# PWR_PROT.net
KiCad netlist of a schematic drawn in Altium Designer
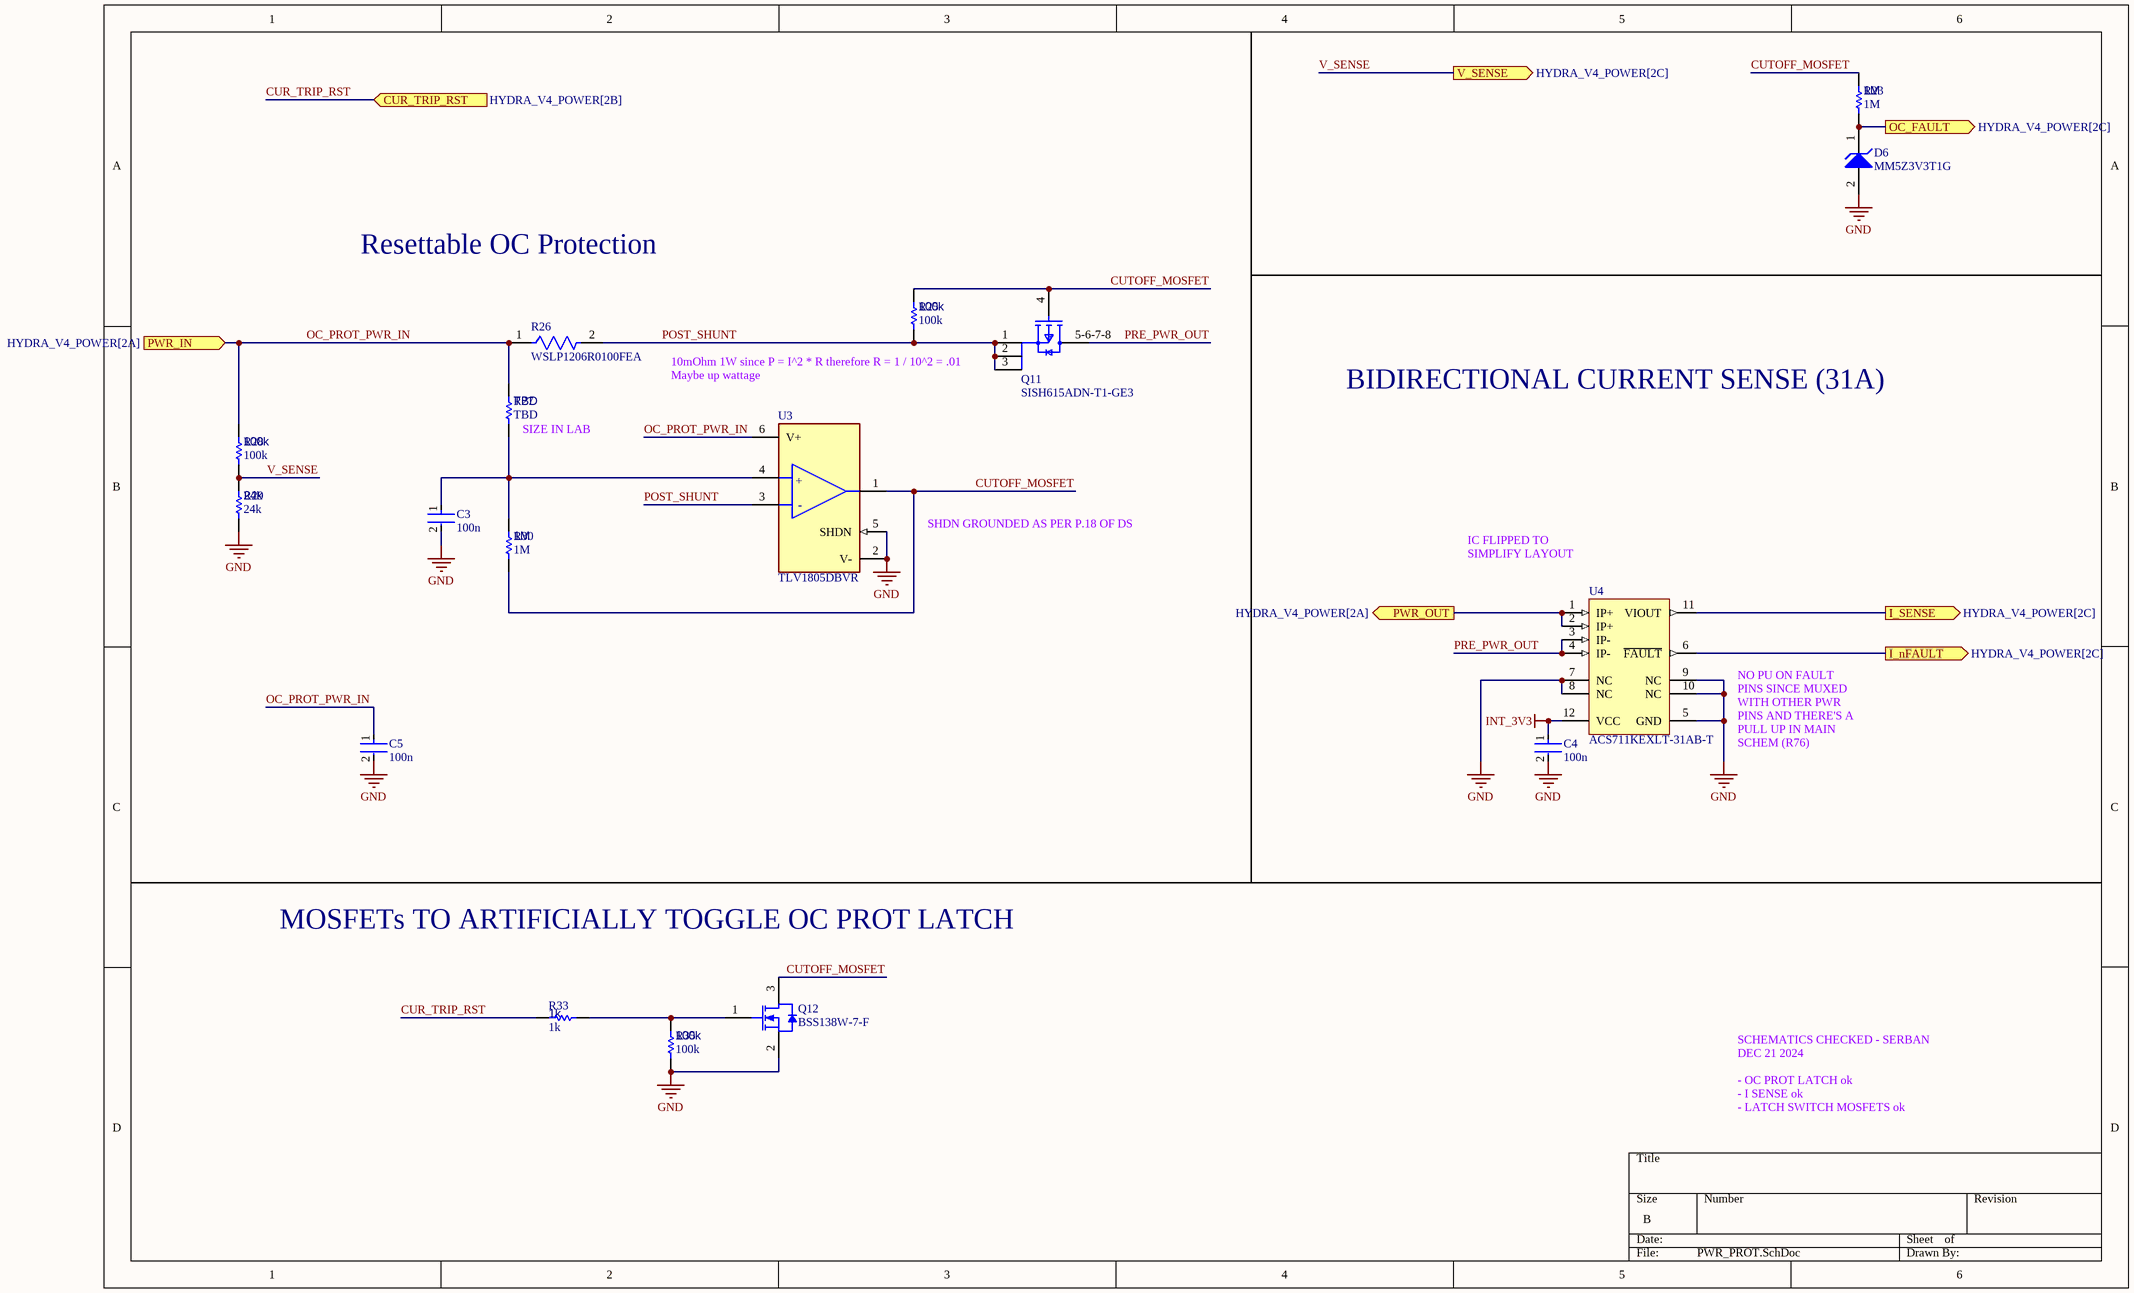
[diagram p0: PWR_PROT.SchDoc]

(export (version "E")
  (design (tool "Eeschema 10.0.6"))
  (components
    (comp (ref "C3")
      (value "100n")
      (footprint "FP-0402-L_1_0_0_05-W_0_5-IPC_A")
      (description "LARGE PADS, 0402 CAP, CHANGE COMMENT TO MATCH REAL P/N")
      (libsource (lib "Space Concordia") (part "b4654b650e69147ec39a6b967a45e02"))
    )
    (comp (ref "C4")
      (value "100n")
      (footprint "FP-0402-L_1_0_0_05-W_0_5-IPC_A")
      (description "LARGE PADS, 0402 CAP, CHANGE COMMENT TO MATCH REAL P/N")
      (libsource (lib "Space Concordia") (part "b4654b650e69147ec39a6b967a45e02"))
    )
    (comp (ref "C5")
      (value "100n")
      (footprint "FP-0402-L_1_0_0_05-W_0_5-IPC_A")
      (description "LARGE PADS, 0402 CAP, CHANGE COMMENT TO MATCH REAL P/N")
      (libsource (lib "Space Concordia") (part "b4654b650e69147ec39a6b967a45e02"))
    )
    (comp (ref "D6")
      (value "MM5Z3V3T1G")
      (footprint "ONSC-SOD-523-2-502-01_V")
      (description "Zener Voltage Regulator, 500 mW, 2-Pin SOD-523, Pb-Free, Tape and Reel")
      (fields (field (name "MANUFACTURER") "On Semiconductor"))
      (libsource (lib "Altium Content Vault") (part "ONSC-K1A2-2"))
    )
    (comp (ref "Q11")
      (value "SISH615ADN-T1-GE3")
      (footprint "SISH615ADN-T1-GE3-Footprint-1")
      (description "Trans MOSFET P-CH 20V 22.1A 8-Pin PowerPAK 1212 EP T/R")
      (libsource (lib "Space Concordia") (part "CMP-013-00036-4"))
    )
    (comp (ref "Q12")
      (value "BSS138W-7-F")
      (footprint "DIOD-SOT323-3_V")
      (fields (field (name "MANUFACTURER") "DiodesIncorporated"))
      (libsource (lib "Altium Content Vault") (part "NEMOS-GSD-3"))
    )
    (comp (ref "R23")
      (value "1M")
      (footprint "R0603B")
      (description "Resistor")
      (fields (field (name "ALTIUM_VALUE") "1M"))
      (libsource (lib "Space Concordia") (part "Resistor"))
    )
    (comp (ref "R25")
      (value "100k")
      (footprint "R0603B")
      (description "Resistor")
      (fields (field (name "ALTIUM_VALUE") "100k"))
      (libsource (lib "Space Concordia") (part "Resistor"))
    )
    (comp (ref "R26")
      (value "WSLP1206R0100FEA")
      (footprint "FP-WSLP1206-FP_1_65x1_93x-MFG")
      (description "RES 0.01 OHM 1% 1W 1206")
      (fields (field (name "TOLERANCE") "1%"))
      (libsource (lib "Altium Content Vault") (part "1029c3af85768c4190bb7ad29bc67b5"))
    )
    (comp (ref "R27")
      (value "TBD")
      (footprint "R0603B")
      (description "Resistor")
      (fields (field (name "ALTIUM_VALUE") "TBD"))
      (libsource (lib "Space Concordia") (part "Resistor"))
    )
    (comp (ref "R28")
      (value "100k")
      (footprint "R0603B")
      (description "Resistor")
      (fields (field (name "ALTIUM_VALUE") "100k"))
      (libsource (lib "Space Concordia") (part "Resistor"))
    )
    (comp (ref "R29")
      (value "24k")
      (footprint "R0603B")
      (description "Resistor")
      (fields (field (name "ALTIUM_VALUE") "24k"))
      (libsource (lib "Space Concordia") (part "Resistor"))
    )
    (comp (ref "R30")
      (value "1M")
      (footprint "R0603B")
      (description "Resistor")
      (fields (field (name "ALTIUM_VALUE") "1M"))
      (libsource (lib "Space Concordia") (part "Resistor"))
    )
    (comp (ref "R33")
      (value "1k")
      (footprint "R0603B")
      (description "Resistor")
      (fields (field (name "ALTIUM_VALUE") "1k"))
      (libsource (lib "Space Concordia") (part "Resistor"))
    )
    (comp (ref "R35")
      (value "100k")
      (footprint "R0603B")
      (description "Resistor")
      (fields (field (name "ALTIUM_VALUE") "100k"))
      (libsource (lib "Space Concordia") (part "Resistor"))
    )
    (comp (ref "U3")
      (value "TLV1805DBVR")
      (footprint "FP-DBV0006A-IPC_C")
      (description "40V, RAIL-TO-RAIL INPUT, PUSH-PU")
      (libsource (lib "Altium Content Vault") (part "c7aa3bc3dbf0dc8b0b0354779bd1228"))
    )
    (comp (ref "U4")
      (value "ACS711KEXLT-31AB-T")
      (footprint "ALEG-EX-12_V")
      (libsource (lib "Altium Content Vault") (part "ALEG-ACS711-QFN-12"))
    )
  )
  (nets
    (net (code "1") (name "/CUR_TRIP_RST") (class "Default")
      (node (ref "R33") (pin "2") (pinfunction "2_2") (pintype "passive"))
    )
    (net (code "2") (name "/CUTOFF_MOSFET") (class "Default")
      (node (ref "Q11") (pin "4") (pinfunction "G_4") (pintype "passive"))
      (node (ref "Q12") (pin "3") (pinfunction "D_3") (pintype "passive"))
      (node (ref "R23") (pin "2") (pinfunction "2_2") (pintype "passive"))
      (node (ref "R25") (pin "2") (pinfunction "2_2") (pintype "passive"))
      (node (ref "R30") (pin "1") (pinfunction "1_1") (pintype "passive"))
      (node (ref "U3") (pin "1") (pinfunction "OUT_1") (pintype "passive"))
    )
    (net (code "3") (name "/I_SENSE") (class "Default")
      (node (ref "U4") (pin "11") (pinfunction "VIOUT_11") (pintype "output"))
    )
    (net (code "4") (name "/I_nFAULT") (class "Default")
      (node (ref "U4") (pin "6") (pinfunction "~{FAULT}_6") (pintype "output"))
    )
    (net (code "5") (name "/OC_FAULT") (class "Default")
      (node (ref "D6") (pin "1") (pinfunction "K_1") (pintype "passive"))
      (node (ref "R23") (pin "1") (pinfunction "1_1") (pintype "passive"))
    )
    (net (code "6") (name "/OC_PROT_PWR_IN") (class "Default")
      (node (ref "C5") (pin "1") (pinfunction "1_1") (pintype "passive"))
      (node (ref "R26") (pin "1") (pinfunction "1_1") (pintype "passive"))
      (node (ref "R27") (pin "2") (pinfunction "2_2") (pintype "passive"))
      (node (ref "R28") (pin "2") (pinfunction "2_2") (pintype "passive"))
      (node (ref "U3") (pin "6") (pinfunction "V+_6") (pintype "power_in"))
    )
    (net (code "7") (name "/POST_SHUNT") (class "Default")
      (node (ref "Q11") (pin "1") (pinfunction "S_1") (pintype "passive"))
      (node (ref "Q11") (pin "2") (pinfunction "S_2") (pintype "passive"))
      (node (ref "Q11") (pin "3") (pinfunction "S_3") (pintype "passive"))
      (node (ref "R25") (pin "1") (pinfunction "1_1") (pintype "passive"))
      (node (ref "R26") (pin "2") (pinfunction "2_2") (pintype "passive"))
      (node (ref "U3") (pin "3") (pinfunction "-IN_3") (pintype "tri_state"))
    )
    (net (code "8") (name "/PRE_PWR_OUT") (class "Default")
      (node (ref "Q11") (pin "5-6-7-8") (pinfunction "D_5-6-7-8") (pintype "passive"))
      (node (ref "U4") (pin "3") (pinfunction "IP-_3") (pintype "input"))
      (node (ref "U4") (pin "4") (pinfunction "IP-_4") (pintype "input"))
    )
    (net (code "9") (name "/PWR_OUT") (class "Default")
      (node (ref "U4") (pin "1") (pinfunction "IP+_1") (pintype "input"))
      (node (ref "U4") (pin "2") (pinfunction "IP+_2") (pintype "input"))
    )
    (net (code "10") (name "/V_SENSE") (class "Default")
      (node (ref "R28") (pin "1") (pinfunction "1_1") (pintype "passive"))
      (node (ref "R29") (pin "2") (pinfunction "2_2") (pintype "passive"))
    )
    (net (code "11") (name "GND") (class "Default")
      (node (ref "C3") (pin "2") (pinfunction "2_2") (pintype "passive"))
      (node (ref "C4") (pin "2") (pinfunction "2_2") (pintype "passive"))
      (node (ref "C5") (pin "2") (pinfunction "2_2") (pintype "passive"))
      (node (ref "D6") (pin "2") (pinfunction "A_2") (pintype "passive"))
      (node (ref "Q12") (pin "2") (pinfunction "S_2") (pintype "passive"))
      (node (ref "R29") (pin "1") (pinfunction "1_1") (pintype "passive"))
      (node (ref "R35") (pin "1") (pinfunction "1_1") (pintype "passive"))
      (node (ref "U3") (pin "2") (pinfunction "V-_2") (pintype "power_in"))
      (node (ref "U3") (pin "5") (pinfunction "SHDN_5") (pintype "input"))
      (node (ref "U4") (pin "10") (pinfunction "NC_10") (pintype "passive"))
      (node (ref "U4") (pin "5") (pinfunction "GND_5") (pintype "power_in"))
      (node (ref "U4") (pin "7") (pinfunction "NC_7") (pintype "passive"))
      (node (ref "U4") (pin "8") (pinfunction "NC_8") (pintype "passive"))
      (node (ref "U4") (pin "9") (pinfunction "NC_9") (pintype "passive"))
    )
    (net (code "12") (name "INT_3V3") (class "Default")
      (node (ref "C4") (pin "1") (pinfunction "1_1") (pintype "passive"))
      (node (ref "U4") (pin "12") (pinfunction "VCC_12") (pintype "power_in"))
    )
    (net (code "13") (name "Net-(Q12-G)") (class "Default")
      (node (ref "Q12") (pin "1") (pinfunction "G_1") (pintype "passive"))
      (node (ref "R33") (pin "1") (pinfunction "1_1") (pintype "passive"))
      (node (ref "R35") (pin "2") (pinfunction "2_2") (pintype "passive"))
    )
    (net (code "14") (name "Net-(U3-+IN)") (class "Default")
      (node (ref "C3") (pin "1") (pinfunction "1_1") (pintype "passive"))
      (node (ref "R27") (pin "1") (pinfunction "1_1") (pintype "passive"))
      (node (ref "R30") (pin "2") (pinfunction "2_2") (pintype "passive"))
      (node (ref "U3") (pin "4") (pinfunction "+IN_4") (pintype "tri_state"))
    )
  )
)
